# APRS.net
KiCad netlist of a schematic drawn in EAGLE
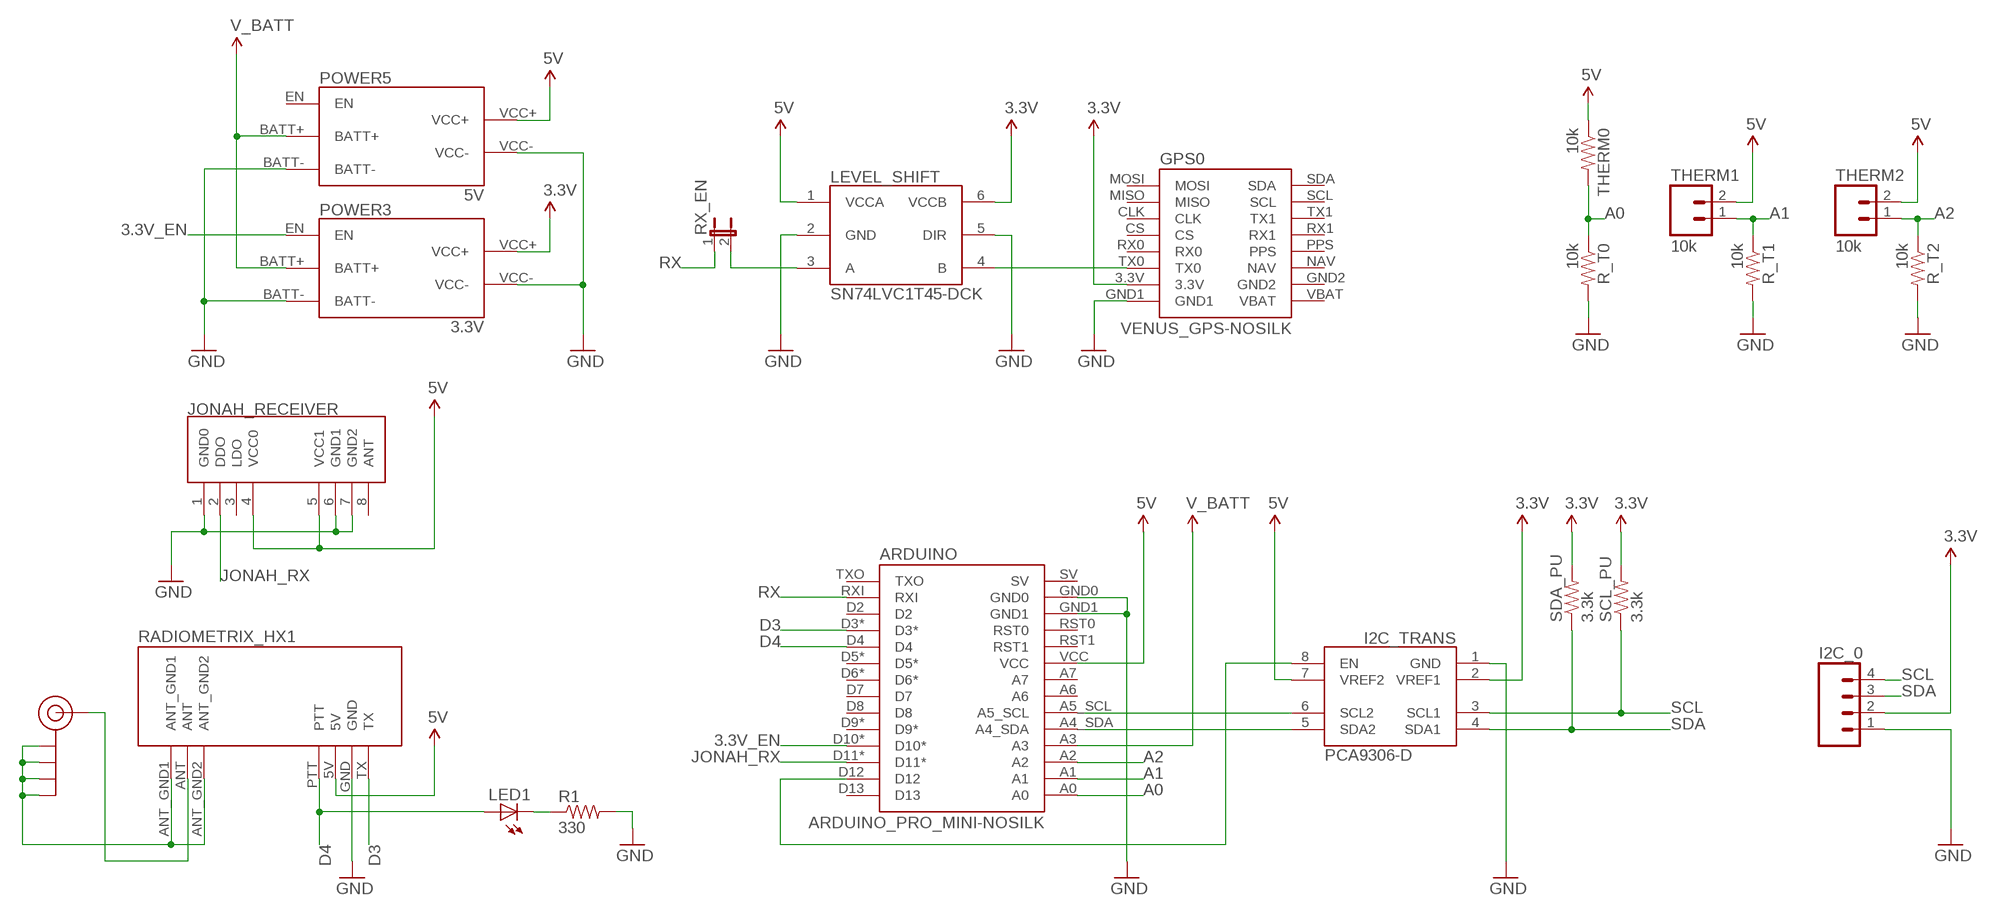
[diagram p0: schematic, sheet 1]

(export (version "E")
  (design (tool "Eeschema 10.0.6"))
  (components
    (comp (ref "ARDUINO")
      (value "ARDUINO_PRO_MINI-NOSILK")
      (footprint "eagle-import:ARDUINO_PRO_MINI-NOSILK")
      (libsource (lib "eagle-import") (part "ARDUINO_PRO_MINI-NOSILK"))
    )
    (comp (ref "GPS0")
      (value "VENUS_GPS-NOSILK")
      (footprint "eagle-import:VENUS_GPS-NOSILK")
      (libsource (lib "eagle-import") (part "VENUS_GPS-NOSILK"))
    )
    (comp (ref "I2C_0")
      (value "M04PTH")
      (footprint "eagle-import:1X04")
      (libsource (lib "eagle-import") (part "M04PTH"))
    )
    (comp (ref "I2C_TRANS")
      (value "PCA9306-D")
      (footprint "eagle-import:SO8")
      (libsource (lib "eagle-import") (part "PCA9306-D"))
    )
    (comp (ref "J$1")
      (value "SMA_EDGE")
      (footprint "eagle-import:SMA-EDGE")
      (libsource (lib "eagle-import") (part "SMA_EDGE"))
    )
    (comp (ref "JONAH_RECEIVER")
      (value "RADIO-KLP-RECEIVER-NOSILK")
      (footprint "eagle-import:RADIO-KLP-RECEIVER-NOSILK")
      (libsource (lib "eagle-import") (part "RADIO-KLP-RECEIVER-NOSILK"))
    )
    (comp (ref "LED1")
      (value "LED0603")
      (footprint "eagle-import:LED-0603")
      (libsource (lib "eagle-import") (part "LED0603"))
    )
    (comp (ref "LEVEL_SHIFT")
      (value "SN74LVC1T45-DCK")
      (footprint "eagle-import:SC70")
      (libsource (lib "eagle-import") (part "SN74LVC1T45-DCK"))
    )
    (comp (ref "POWER3")
      (value "3.3V")
      (footprint "eagle-import:POWER-TPS6300X-NOSILK")
      (libsource (lib "eagle-import") (part "POWER-TPS6300X-NOSILK"))
    )
    (comp (ref "POWER5")
      (value "5V")
      (footprint "eagle-import:POWER-TPS6300X-NOSILK")
      (libsource (lib "eagle-import") (part "POWER-TPS6300X-NOSILK"))
    )
    (comp (ref "R1")
      (value "330")
      (footprint "eagle-import:0805")
      (libsource (lib "eagle-import") (part "RESISTOR0805-RES"))
    )
    (comp (ref "RADIOMETRIX_HX1")
      (value "RADIOMETRIX-HX1")
      (footprint "eagle-import:RADIOMETRIX-HX1")
      (libsource (lib "eagle-import") (part "RADIOMETRIX-HX1"))
    )
    (comp (ref "RX_EN")
      (value "JUMPER-2PTH")
      (footprint "eagle-import:1X02")
      (libsource (lib "eagle-import") (part "JUMPER-2PTH"))
    )
    (comp (ref "R_T0")
      (value "10k")
      (footprint "eagle-import:0805")
      (libsource (lib "eagle-import") (part "RESISTOR0805-RES"))
    )
    (comp (ref "R_T1")
      (value "10k")
      (footprint "eagle-import:0805")
      (libsource (lib "eagle-import") (part "RESISTOR0805-RES"))
    )
    (comp (ref "R_T2")
      (value "10k")
      (footprint "eagle-import:0805")
      (libsource (lib "eagle-import") (part "RESISTOR0805-RES"))
    )
    (comp (ref "SCL_PU")
      (value "3.3k")
      (footprint "eagle-import:0805")
      (libsource (lib "eagle-import") (part "RESISTOR0805-RES"))
    )
    (comp (ref "SDA_PU")
      (value "3.3k")
      (footprint "eagle-import:0805")
      (libsource (lib "eagle-import") (part "RESISTOR0805-RES"))
    )
    (comp (ref "THERM0")
      (value "10k")
      (footprint "eagle-import:0805")
      (libsource (lib "eagle-import") (part "RESISTOR0805-RES"))
    )
    (comp (ref "THERM1")
      (value "10k")
      (footprint "eagle-import:JST-2-PTH")
      (libsource (lib "eagle-import") (part "M02JST-PTH-2"))
    )
    (comp (ref "THERM2")
      (value "10k")
      (footprint "eagle-import:JST-2-PTH")
      (libsource (lib "eagle-import") (part "M02JST-PTH-2"))
    )
  )
  (nets
    (net (code "1") (name "/3.3V_EN") (class "Default")
      (node (ref "ARDUINO") (pin "D10*") (pinfunction "D10*_D10*") (pintype "bidirectional"))
      (node (ref "POWER3") (pin "EN") (pinfunction "EN_EN") (pintype "bidirectional"))
    )
    (net (code "2") (name "/A0") (class "Default")
      (node (ref "ARDUINO") (pin "A0") (pinfunction "A0_A0") (pintype "bidirectional"))
      (node (ref "R_T0") (pin "1") (pinfunction "1_1") (pintype "passive"))
      (node (ref "THERM0") (pin "2") (pinfunction "2_2") (pintype "passive"))
    )
    (net (code "3") (name "/A1") (class "Default")
      (node (ref "ARDUINO") (pin "A1") (pinfunction "A1_A1") (pintype "bidirectional"))
      (node (ref "R_T1") (pin "1") (pinfunction "1_1") (pintype "passive"))
      (node (ref "THERM1") (pin "1") (pinfunction "1_1") (pintype "passive"))
    )
    (net (code "4") (name "/A2") (class "Default")
      (node (ref "ARDUINO") (pin "A2") (pinfunction "A2_A2") (pintype "bidirectional"))
      (node (ref "R_T2") (pin "1") (pinfunction "1_1") (pintype "passive"))
      (node (ref "THERM2") (pin "1") (pinfunction "1_1") (pintype "passive"))
    )
    (net (code "5") (name "/D3") (class "Default")
      (node (ref "ARDUINO") (pin "D3*") (pinfunction "D3*_D3*") (pintype "bidirectional"))
      (node (ref "RADIOMETRIX_HX1") (pin "TX") (pinfunction "TX_TX") (pintype "bidirectional"))
    )
    (net (code "6") (name "/D4") (class "Default")
      (node (ref "ARDUINO") (pin "D4") (pinfunction "D4_D4") (pintype "bidirectional"))
      (node (ref "LED1") (pin "A") (pinfunction "A_A") (pintype "passive"))
      (node (ref "RADIOMETRIX_HX1") (pin "PTT") (pinfunction "PTT_PTT") (pintype "bidirectional"))
    )
    (net (code "7") (name "/JONAH_RX") (class "Default")
      (node (ref "ARDUINO") (pin "D11*") (pinfunction "D11*_D11*") (pintype "bidirectional"))
      (node (ref "JONAH_RECEIVER") (pin "2") (pinfunction "DDO_2") (pintype "bidirectional"))
    )
    (net (code "8") (name "/RX") (class "Default")
      (node (ref "ARDUINO") (pin "RXI") (pinfunction "RXI_RXI") (pintype "bidirectional"))
      (node (ref "RX_EN") (pin "1") (pinfunction "1_1") (pintype "passive"))
    )
    (net (code "9") (name "/SCL") (class "Default")
      (node (ref "I2C_0") (pin "4") (pinfunction "4_4") (pintype "passive"))
      (node (ref "I2C_TRANS") (pin "3") (pinfunction "SCL1_3") (pintype "bidirectional"))
      (node (ref "SCL_PU") (pin "1") (pinfunction "1_1") (pintype "passive"))
    )
    (net (code "10") (name "/SDA") (class "Default")
      (node (ref "I2C_0") (pin "3") (pinfunction "3_3") (pintype "passive"))
      (node (ref "I2C_TRANS") (pin "4") (pinfunction "SDA1_4") (pintype "bidirectional"))
      (node (ref "SDA_PU") (pin "1") (pinfunction "1_1") (pintype "passive"))
    )
    (net (code "11") (name "3.3V") (class "Default")
      (node (ref "GPS0") (pin "3.3V") (pinfunction "3.3V_3.3V") (pintype "bidirectional"))
      (node (ref "I2C_0") (pin "2") (pinfunction "2_2") (pintype "passive"))
      (node (ref "I2C_TRANS") (pin "2") (pinfunction "VREF1_2") (pintype "bidirectional"))
      (node (ref "LEVEL_SHIFT") (pin "6") (pinfunction "VCCB_6") (pintype "bidirectional"))
      (node (ref "POWER3") (pin "VCC+") (pinfunction "VCC+_VCC+") (pintype "bidirectional"))
      (node (ref "SCL_PU") (pin "2") (pinfunction "2_2") (pintype "passive"))
      (node (ref "SDA_PU") (pin "2") (pinfunction "2_2") (pintype "passive"))
    )
    (net (code "12") (name "5V") (class "Default")
      (node (ref "ARDUINO") (pin "VCC") (pinfunction "VCC_VCC") (pintype "bidirectional"))
      (node (ref "I2C_TRANS") (pin "7") (pinfunction "VREF2_7") (pintype "bidirectional"))
      (node (ref "JONAH_RECEIVER") (pin "4") (pinfunction "VCC0_4") (pintype "bidirectional"))
      (node (ref "JONAH_RECEIVER") (pin "5") (pinfunction "VCC1_5") (pintype "bidirectional"))
      (node (ref "LEVEL_SHIFT") (pin "1") (pinfunction "VCCA_1") (pintype "bidirectional"))
      (node (ref "POWER5") (pin "VCC+") (pinfunction "VCC+_VCC+") (pintype "bidirectional"))
      (node (ref "RADIOMETRIX_HX1") (pin "5V") (pinfunction "5V_5V") (pintype "bidirectional"))
      (node (ref "THERM0") (pin "1") (pinfunction "1_1") (pintype "passive"))
      (node (ref "THERM1") (pin "2") (pinfunction "2_2") (pintype "passive"))
      (node (ref "THERM2") (pin "2") (pinfunction "2_2") (pintype "passive"))
    )
    (net (code "13") (name "GND") (class "Default")
      (node (ref "ARDUINO") (pin "GND0") (pinfunction "GND0_GND0") (pintype "bidirectional"))
      (node (ref "ARDUINO") (pin "GND1") (pinfunction "GND1_GND1") (pintype "bidirectional"))
      (node (ref "GPS0") (pin "GND1") (pinfunction "GND1_GND1") (pintype "bidirectional"))
      (node (ref "I2C_0") (pin "1") (pinfunction "1_1") (pintype "passive"))
      (node (ref "I2C_TRANS") (pin "1") (pinfunction "GND_1") (pintype "bidirectional"))
      (node (ref "JONAH_RECEIVER") (pin "1") (pinfunction "GND0_1") (pintype "bidirectional"))
      (node (ref "JONAH_RECEIVER") (pin "6") (pinfunction "GND1_6") (pintype "bidirectional"))
      (node (ref "JONAH_RECEIVER") (pin "7") (pinfunction "GND2_7") (pintype "bidirectional"))
      (node (ref "LEVEL_SHIFT") (pin "2") (pinfunction "GND_2") (pintype "bidirectional"))
      (node (ref "LEVEL_SHIFT") (pin "5") (pinfunction "DIR_5") (pintype "bidirectional"))
      (node (ref "POWER3") (pin "BATT-") (pinfunction "BATT-_BATT-") (pintype "bidirectional"))
      (node (ref "POWER3") (pin "VCC-") (pinfunction "VCC-_VCC-") (pintype "bidirectional"))
      (node (ref "POWER5") (pin "BATT-") (pinfunction "BATT-_BATT-") (pintype "bidirectional"))
      (node (ref "POWER5") (pin "VCC-") (pinfunction "VCC-_VCC-") (pintype "bidirectional"))
      (node (ref "R1") (pin "2") (pinfunction "2_2") (pintype "passive"))
      (node (ref "RADIOMETRIX_HX1") (pin "GND") (pinfunction "GND_GND") (pintype "bidirectional"))
      (node (ref "R_T0") (pin "2") (pinfunction "2_2") (pintype "passive"))
      (node (ref "R_T1") (pin "2") (pinfunction "2_2") (pintype "passive"))
      (node (ref "R_T2") (pin "2") (pinfunction "2_2") (pintype "passive"))
    )
    (net (code "14") (name "Net-(I2C_TRANS-EN)") (class "Default")
      (node (ref "ARDUINO") (pin "D12") (pinfunction "D12_D12") (pintype "bidirectional"))
      (node (ref "I2C_TRANS") (pin "8") (pinfunction "EN_8") (pintype "bidirectional"))
    )
    (net (code "15") (name "Net-(I2C_TRANS-SCL2)") (class "Default")
      (node (ref "ARDUINO") (pin "A5_SCL") (pinfunction "A5_SCL_A5_SCL") (pintype "bidirectional"))
      (node (ref "I2C_TRANS") (pin "6") (pinfunction "SCL2_6") (pintype "bidirectional"))
    )
    (net (code "16") (name "Net-(I2C_TRANS-SDA2)") (class "Default")
      (node (ref "ARDUINO") (pin "A4_SDA") (pinfunction "A4_SDA_A4_SDA") (pintype "bidirectional"))
      (node (ref "I2C_TRANS") (pin "5") (pinfunction "SDA2_5") (pintype "bidirectional"))
    )
    (net (code "17") (name "Net-(J$1-GND-PadGND@0)") (class "Default")
      (node (ref "J$1") (pin "GND@0") (pinfunction "GND_GND@0") (pintype "bidirectional"))
      (node (ref "J$1") (pin "GND@1") (pinfunction "GND_GND@1") (pintype "bidirectional"))
      (node (ref "J$1") (pin "GND@2") (pinfunction "GND_GND@2") (pintype "bidirectional"))
      (node (ref "J$1") (pin "GND@3") (pinfunction "GND_GND@3") (pintype "bidirectional"))
      (node (ref "RADIOMETRIX_HX1") (pin "ANT_GND1") (pinfunction "ANT_GND1_ANT_GND1") (pintype "bidirectional"))
      (node (ref "RADIOMETRIX_HX1") (pin "ANT_GND2") (pinfunction "ANT_GND2_ANT_GND2") (pintype "bidirectional"))
    )
    (net (code "18") (name "Net-(J$1-SIGNAL)") (class "Default")
      (node (ref "J$1") (pin "SIG") (pinfunction "SIGNAL_SIG") (pintype "bidirectional"))
      (node (ref "RADIOMETRIX_HX1") (pin "ANT") (pinfunction "ANT_ANT") (pintype "bidirectional"))
    )
    (net (code "19") (name "Net-(LED1-PadC)") (class "Default")
      (node (ref "LED1") (pin "C") (pinfunction "C_C") (pintype "passive"))
      (node (ref "R1") (pin "1") (pinfunction "1_1") (pintype "passive"))
    )
    (net (code "20") (name "Net-(LEVEL_SHIFT-A)") (class "Default")
      (node (ref "LEVEL_SHIFT") (pin "3") (pinfunction "A_3") (pintype "bidirectional"))
      (node (ref "RX_EN") (pin "2") (pinfunction "2_2") (pintype "passive"))
    )
    (net (code "21") (name "Net-(LEVEL_SHIFT-B)") (class "Default")
      (node (ref "GPS0") (pin "TX0") (pinfunction "TX0_TX0") (pintype "bidirectional"))
      (node (ref "LEVEL_SHIFT") (pin "4") (pinfunction "B_4") (pintype "bidirectional"))
    )
    (net (code "22") (name "V_BATT") (class "Default")
      (node (ref "ARDUINO") (pin "A3") (pinfunction "A3_A3") (pintype "bidirectional"))
      (node (ref "POWER3") (pin "BATT+") (pinfunction "BATT+_BATT+") (pintype "bidirectional"))
      (node (ref "POWER5") (pin "BATT+") (pinfunction "BATT+_BATT+") (pintype "bidirectional"))
    )
    (net (code "23") (name "unconnected-(ARDUINO-PadA6)") (class "Default")
      (node (ref "ARDUINO") (pin "A6") (pinfunction "A6_A6") (pintype "bidirectional"))
    )
    (net (code "24") (name "unconnected-(ARDUINO-PadA7)") (class "Default")
      (node (ref "ARDUINO") (pin "A7") (pinfunction "A7_A7") (pintype "bidirectional"))
    )
    (net (code "25") (name "unconnected-(ARDUINO-PadD2)") (class "Default")
      (node (ref "ARDUINO") (pin "D2") (pinfunction "D2_D2") (pintype "bidirectional"))
    )
    (net (code "26") (name "unconnected-(ARDUINO-PadD5*)") (class "Default")
      (node (ref "ARDUINO") (pin "D5*") (pinfunction "D5*_D5*") (pintype "bidirectional"))
    )
    (net (code "27") (name "unconnected-(ARDUINO-PadD6*)") (class "Default")
      (node (ref "ARDUINO") (pin "D6*") (pinfunction "D6*_D6*") (pintype "bidirectional"))
    )
    (net (code "28") (name "unconnected-(ARDUINO-PadD7)") (class "Default")
      (node (ref "ARDUINO") (pin "D7") (pinfunction "D7_D7") (pintype "bidirectional"))
    )
    (net (code "29") (name "unconnected-(ARDUINO-PadD8)") (class "Default")
      (node (ref "ARDUINO") (pin "D8") (pinfunction "D8_D8") (pintype "bidirectional"))
    )
    (net (code "30") (name "unconnected-(ARDUINO-PadD9*)") (class "Default")
      (node (ref "ARDUINO") (pin "D9*") (pinfunction "D9*_D9*") (pintype "bidirectional"))
    )
    (net (code "31") (name "unconnected-(ARDUINO-PadD13)") (class "Default")
      (node (ref "ARDUINO") (pin "D13") (pinfunction "D13_D13") (pintype "bidirectional"))
    )
    (net (code "32") (name "unconnected-(ARDUINO-PadRST0)") (class "Default")
      (node (ref "ARDUINO") (pin "RST0") (pinfunction "RST0_RST0") (pintype "bidirectional"))
    )
    (net (code "33") (name "unconnected-(ARDUINO-PadRST1)") (class "Default")
      (node (ref "ARDUINO") (pin "RST1") (pinfunction "RST1_RST1") (pintype "bidirectional"))
    )
    (net (code "34") (name "unconnected-(ARDUINO-PadSV)") (class "Default")
      (node (ref "ARDUINO") (pin "SV") (pinfunction "SV_SV") (pintype "bidirectional"))
    )
    (net (code "35") (name "unconnected-(ARDUINO-PadTXO)") (class "Default")
      (node (ref "ARDUINO") (pin "TXO") (pinfunction "TXO_TXO") (pintype "bidirectional"))
    )
    (net (code "36") (name "unconnected-(GPS0-PadCLK)") (class "Default")
      (node (ref "GPS0") (pin "CLK") (pinfunction "CLK_CLK") (pintype "bidirectional"))
    )
    (net (code "37") (name "unconnected-(GPS0-PadCS)") (class "Default")
      (node (ref "GPS0") (pin "CS") (pinfunction "CS_CS") (pintype "bidirectional"))
    )
    (net (code "38") (name "unconnected-(GPS0-PadGND2)") (class "Default")
      (node (ref "GPS0") (pin "GND2") (pinfunction "GND2_GND2") (pintype "bidirectional"))
    )
    (net (code "39") (name "unconnected-(GPS0-PadMISO)") (class "Default")
      (node (ref "GPS0") (pin "MISO") (pinfunction "MISO_MISO") (pintype "bidirectional"))
    )
    (net (code "40") (name "unconnected-(GPS0-PadMOSI)") (class "Default")
      (node (ref "GPS0") (pin "MOSI") (pinfunction "MOSI_MOSI") (pintype "bidirectional"))
    )
    (net (code "41") (name "unconnected-(GPS0-PadNAV)") (class "Default")
      (node (ref "GPS0") (pin "NAV") (pinfunction "NAV_NAV") (pintype "bidirectional"))
    )
    (net (code "42") (name "unconnected-(GPS0-PadPPS)") (class "Default")
      (node (ref "GPS0") (pin "PPS") (pinfunction "PPS_PPS") (pintype "bidirectional"))
    )
    (net (code "43") (name "unconnected-(GPS0-PadRX0)") (class "Default")
      (node (ref "GPS0") (pin "RX0") (pinfunction "RX0_RX0") (pintype "bidirectional"))
    )
    (net (code "44") (name "unconnected-(GPS0-PadRX1)") (class "Default")
      (node (ref "GPS0") (pin "RX1") (pinfunction "RX1_RX1") (pintype "bidirectional"))
    )
    (net (code "45") (name "unconnected-(GPS0-PadSCL)") (class "Default")
      (node (ref "GPS0") (pin "SCL") (pinfunction "SCL_SCL") (pintype "bidirectional"))
    )
    (net (code "46") (name "unconnected-(GPS0-PadSDA)") (class "Default")
      (node (ref "GPS0") (pin "SDA") (pinfunction "SDA_SDA") (pintype "bidirectional"))
    )
    (net (code "47") (name "unconnected-(GPS0-PadTX1)") (class "Default")
      (node (ref "GPS0") (pin "TX1") (pinfunction "TX1_TX1") (pintype "bidirectional"))
    )
    (net (code "48") (name "unconnected-(GPS0-PadVBAT)") (class "Default")
      (node (ref "GPS0") (pin "VBAT") (pinfunction "VBAT_VBAT") (pintype "bidirectional"))
    )
    (net (code "49") (name "unconnected-(JONAH_RECEIVER-ANT-Pad8)") (class "Default")
      (node (ref "JONAH_RECEIVER") (pin "8") (pinfunction "ANT_8") (pintype "bidirectional"))
    )
    (net (code "50") (name "unconnected-(JONAH_RECEIVER-LDO-Pad3)") (class "Default")
      (node (ref "JONAH_RECEIVER") (pin "3") (pinfunction "LDO_3") (pintype "bidirectional"))
    )
    (net (code "51") (name "unconnected-(POWER5-PadEN)") (class "Default")
      (node (ref "POWER5") (pin "EN") (pinfunction "EN_EN") (pintype "bidirectional"))
    )
  )
)
